# untitled.net
KiCad netlist of a schematic drawn in EAGLE
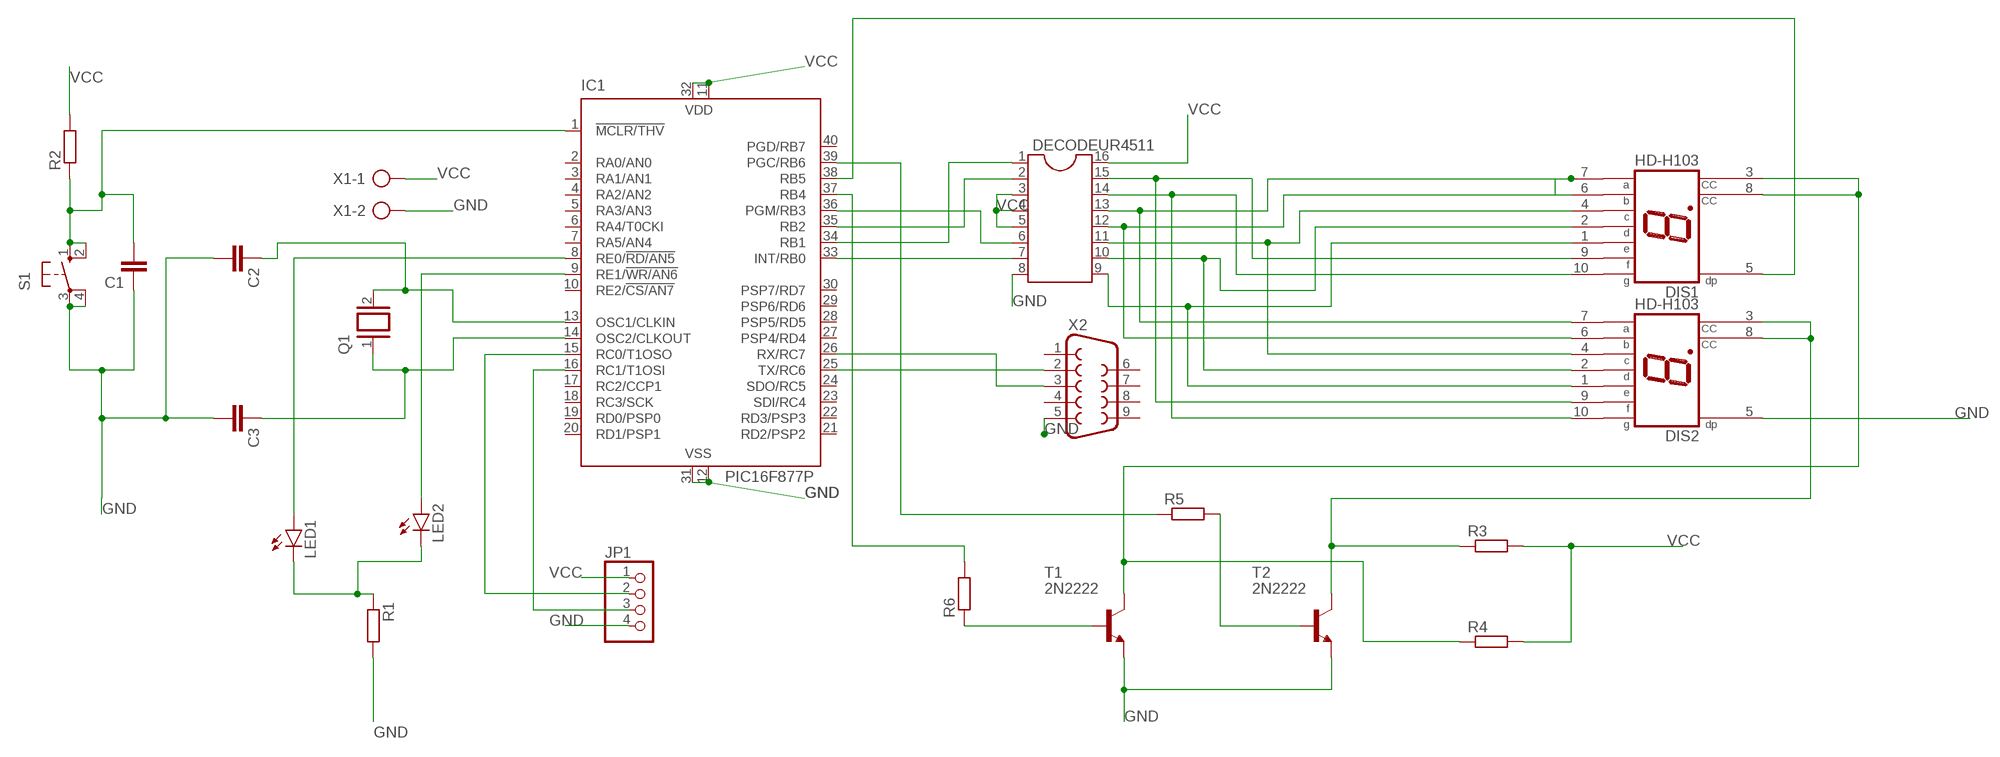
[diagram p0: schematic, sheet 1]

(export (version "E")
  (design (tool "Eeschema 10.0.6"))
  (components
    (comp (ref "C1")
      (value "C-EU025-025X050")
      (footprint "eagle-import:C025-025X050")
      (libsource (lib "eagle-import") (part "C-EU025-025X050"))
    )
    (comp (ref "C2")
      (value "C-EU025-025X050")
      (footprint "eagle-import:C025-025X050")
      (libsource (lib "eagle-import") (part "C-EU025-025X050"))
    )
    (comp (ref "C3")
      (value "C-EU025-025X050")
      (footprint "eagle-import:C025-025X050")
      (libsource (lib "eagle-import") (part "C-EU025-025X050"))
    )
    (comp (ref "DECODEUR4511")
      (value "DIL16")
      (footprint "eagle-import:DIL16")
      (libsource (lib "eagle-import") (part "DIL16"))
    )
    (comp (ref "DIS1")
      (value "HD-H103")
      (footprint "eagle-import:HDSP-M")
      (libsource (lib "eagle-import") (part "HD-H103"))
    )
    (comp (ref "DIS2")
      (value "HD-H103")
      (footprint "eagle-import:HDSP-M")
      (libsource (lib "eagle-import") (part "HD-H103"))
    )
    (comp (ref "IC1")
      (value "PIC16F877P")
      (footprint "eagle-import:DIL40")
      (fields (field (name "MF") "MICROCHIP") (field (name "MPN") "PIC16F877-04/P"))
      (libsource (lib "eagle-import") (part "PIC16F87P7"))
    )
    (comp (ref "JP1")
      (value "PINHD-1X4")
      (footprint "eagle-import:1X04")
      (libsource (lib "eagle-import") (part "PINHD-1X4"))
    )
    (comp (ref "LED1")
      (value "LED5MM")
      (footprint "eagle-import:LED5MM")
      (libsource (lib "eagle-import") (part "LED5MM"))
    )
    (comp (ref "LED2")
      (value "LED5MM")
      (footprint "eagle-import:LED5MM")
      (libsource (lib "eagle-import") (part "LED5MM"))
    )
    (comp (ref "Q1")
      (value "XTAL/S")
      (footprint "eagle-import:QS")
      (libsource (lib "eagle-import") (part "XTAL/S"))
    )
    (comp (ref "R1")
      (value "R-EU_0207/10")
      (footprint "eagle-import:0207_10")
      (libsource (lib "eagle-import") (part "R-EU_0207/10"))
    )
    (comp (ref "R2")
      (value "R-EU_0207/10")
      (footprint "eagle-import:0207_10")
      (libsource (lib "eagle-import") (part "R-EU_0207/10"))
    )
    (comp (ref "R3")
      (value "R-EU_0207/10")
      (footprint "eagle-import:0207_10")
      (libsource (lib "eagle-import") (part "R-EU_0207/10"))
    )
    (comp (ref "R4")
      (value "R-EU_0207/10")
      (footprint "eagle-import:0207_10")
      (libsource (lib "eagle-import") (part "R-EU_0207/10"))
    )
    (comp (ref "R5")
      (value "R-EU_0207/10")
      (footprint "eagle-import:0207_10")
      (libsource (lib "eagle-import") (part "R-EU_0207/10"))
    )
    (comp (ref "R6")
      (value "R-EU_0207/10")
      (footprint "eagle-import:0207_10")
      (libsource (lib "eagle-import") (part "R-EU_0207/10"))
    )
    (comp (ref "S1")
      (value "10-XX")
      (footprint "eagle-import:B3F-10XX")
      (fields (field (name "MPN") "B3F-1000"))
      (libsource (lib "eagle-import") (part "10-XX"))
    )
    (comp (ref "T1")
      (value "2N2222")
      (footprint "eagle-import:TO18")
      (libsource (lib "eagle-import") (part "2N2222"))
    )
    (comp (ref "T2")
      (value "2N2222")
      (footprint "eagle-import:TO18")
      (libsource (lib "eagle-import") (part "2N2222"))
    )
    (comp (ref "X1")
      (value "AK300/2")
      (footprint "eagle-import:AK300_2")
      (libsource (lib "eagle-import") (part "AK300/2"))
    )
    (comp (ref "X2")
      (value "F09H")
      (footprint "eagle-import:F09H")
      (libsource (lib "eagle-import") (part "F09H"))
    )
  )
  (nets
    (net (code "1") (name "/GND") (class "Default")
      (node (ref "C1") (pin "1") (pinfunction "1_1") (pintype "passive"))
      (node (ref "C2") (pin "2") (pinfunction "2_2") (pintype "passive"))
      (node (ref "C3") (pin "2") (pinfunction "2_2") (pintype "passive"))
      (node (ref "DECODEUR4511") (pin "8") (pinfunction "8_8") (pintype "passive"))
      (node (ref "DIS2") (pin "5") (pinfunction "DP_5") (pintype "passive"))
      (node (ref "IC1") (pin "12") (pinfunction "VSS_12") (pintype "power_in"))
      (node (ref "IC1") (pin "31") (pinfunction "VSS_31") (pintype "power_in"))
      (node (ref "JP1") (pin "4") (pinfunction "4_4") (pintype "passive"))
      (node (ref "R1") (pin "2") (pinfunction "2_2") (pintype "passive"))
      (node (ref "S1") (pin "3") (pinfunction "P_3") (pintype "passive"))
      (node (ref "S1") (pin "4") (pinfunction "P1_4") (pintype "passive"))
      (node (ref "T1") (pin "1") (pinfunction "E_1") (pintype "passive"))
      (node (ref "T2") (pin "1") (pinfunction "E_1") (pintype "passive"))
      (node (ref "X1") (pin "2") (pinfunction "KL_2") (pintype "passive"))
      (node (ref "X2") (pin "5") (pinfunction "5_5") (pintype "passive"))
    )
    (net (code "2") (name "/VCC") (class "Default")
      (node (ref "DECODEUR4511") (pin "16") (pinfunction "16_16") (pintype "passive"))
      (node (ref "DECODEUR4511") (pin "3") (pinfunction "3_3") (pintype "passive"))
      (node (ref "DECODEUR4511") (pin "4") (pinfunction "4_4") (pintype "passive"))
      (node (ref "DECODEUR4511") (pin "5") (pinfunction "5_5") (pintype "passive"))
      (node (ref "IC1") (pin "11") (pinfunction "VDD_11") (pintype "power_in"))
      (node (ref "IC1") (pin "32") (pinfunction "VDD_32") (pintype "power_in"))
      (node (ref "JP1") (pin "1") (pinfunction "1_1") (pintype "passive"))
      (node (ref "R2") (pin "2") (pinfunction "2_2") (pintype "passive"))
      (node (ref "R3") (pin "2") (pinfunction "2_2") (pintype "passive"))
      (node (ref "R4") (pin "2") (pinfunction "2_2") (pintype "passive"))
      (node (ref "X1") (pin "1") (pinfunction "KL_1") (pintype "passive"))
    )
    (net (code "3") (name "Net-(DIS1-A)") (class "Default")
      (node (ref "DECODEUR4511") (pin "13") (pinfunction "13_13") (pintype "passive"))
      (node (ref "DIS1") (pin "7") (pinfunction "A_7") (pintype "passive"))
      (node (ref "DIS2") (pin "7") (pinfunction "A_7") (pintype "passive"))
    )
    (net (code "4") (name "Net-(DIS1-B)") (class "Default")
      (node (ref "DECODEUR4511") (pin "12") (pinfunction "12_12") (pintype "passive"))
      (node (ref "DIS1") (pin "6") (pinfunction "B_6") (pintype "passive"))
      (node (ref "DIS2") (pin "6") (pinfunction "B_6") (pintype "passive"))
    )
    (net (code "5") (name "Net-(DIS1-C)") (class "Default")
      (node (ref "DECODEUR4511") (pin "11") (pinfunction "11_11") (pintype "passive"))
      (node (ref "DIS1") (pin "4") (pinfunction "C_4") (pintype "passive"))
      (node (ref "DIS2") (pin "4") (pinfunction "C_4") (pintype "passive"))
    )
    (net (code "6") (name "Net-(DIS1-D)") (class "Default")
      (node (ref "DECODEUR4511") (pin "10") (pinfunction "10_10") (pintype "passive"))
      (node (ref "DIS1") (pin "2") (pinfunction "D_2") (pintype "passive"))
      (node (ref "DIS2") (pin "2") (pinfunction "D_2") (pintype "passive"))
    )
    (net (code "7") (name "Net-(DIS1-DP)") (class "Default")
      (node (ref "DIS1") (pin "5") (pinfunction "DP_5") (pintype "passive"))
      (node (ref "IC1") (pin "38") (pinfunction "RB5_38") (pintype "bidirectional"))
    )
    (net (code "8") (name "Net-(DIS1-E)") (class "Default")
      (node (ref "DECODEUR4511") (pin "9") (pinfunction "9_9") (pintype "passive"))
      (node (ref "DIS1") (pin "1") (pinfunction "E_1") (pintype "passive"))
      (node (ref "DIS2") (pin "1") (pinfunction "E_1") (pintype "passive"))
    )
    (net (code "9") (name "Net-(DIS1-F)") (class "Default")
      (node (ref "DECODEUR4511") (pin "15") (pinfunction "15_15") (pintype "passive"))
      (node (ref "DIS1") (pin "9") (pinfunction "F_9") (pintype "passive"))
      (node (ref "DIS2") (pin "9") (pinfunction "F_9") (pintype "passive"))
    )
    (net (code "10") (name "Net-(DIS1-G)") (class "Default")
      (node (ref "DECODEUR4511") (pin "14") (pinfunction "14_14") (pintype "passive"))
      (node (ref "DIS1") (pin "10") (pinfunction "G_10") (pintype "passive"))
      (node (ref "DIS2") (pin "10") (pinfunction "G_10") (pintype "passive"))
    )
    (net (code "11") (name "Net-(IC1-INT{slash}RB0)") (class "Default")
      (node (ref "DECODEUR4511") (pin "7") (pinfunction "7_7") (pintype "passive"))
      (node (ref "IC1") (pin "33") (pinfunction "INT/RB0_33") (pintype "bidirectional"))
    )
    (net (code "12") (name "Net-(IC1-OSC1{slash}CLKIN)") (class "Default")
      (node (ref "C2") (pin "1") (pinfunction "1_1") (pintype "passive"))
      (node (ref "IC1") (pin "13") (pinfunction "OSC1/CLKIN_13") (pintype "input"))
      (node (ref "Q1") (pin "2") (pinfunction "2_2") (pintype "passive"))
    )
    (net (code "13") (name "Net-(IC1-OSC2{slash}CLKOUT)") (class "Default")
      (node (ref "C3") (pin "1") (pinfunction "1_1") (pintype "passive"))
      (node (ref "IC1") (pin "14") (pinfunction "OSC2/CLKOUT_14") (pintype "output"))
      (node (ref "Q1") (pin "1") (pinfunction "1_1") (pintype "passive"))
    )
    (net (code "14") (name "Net-(IC1-PGC{slash}RB6)") (class "Default")
      (node (ref "IC1") (pin "39") (pinfunction "PGC/RB6_39") (pintype "bidirectional"))
      (node (ref "R5") (pin "1") (pinfunction "1_1") (pintype "passive"))
    )
    (net (code "15") (name "Net-(IC1-PGM{slash}RB3)") (class "Default")
      (node (ref "DECODEUR4511") (pin "6") (pinfunction "6_6") (pintype "passive"))
      (node (ref "IC1") (pin "36") (pinfunction "PGM/RB3_36") (pintype "bidirectional"))
    )
    (net (code "16") (name "Net-(IC1-RB1)") (class "Default")
      (node (ref "DECODEUR4511") (pin "1") (pinfunction "1_1") (pintype "passive"))
      (node (ref "IC1") (pin "34") (pinfunction "RB1_34") (pintype "bidirectional"))
    )
    (net (code "17") (name "Net-(IC1-RB2)") (class "Default")
      (node (ref "DECODEUR4511") (pin "2") (pinfunction "2_2") (pintype "passive"))
      (node (ref "IC1") (pin "35") (pinfunction "RB2_35") (pintype "bidirectional"))
    )
    (net (code "18") (name "Net-(IC1-RB4)") (class "Default")
      (node (ref "IC1") (pin "37") (pinfunction "RB4_37") (pintype "bidirectional"))
      (node (ref "R6") (pin "2") (pinfunction "2_2") (pintype "passive"))
    )
    (net (code "19") (name "Net-(IC1-RC0{slash}T1OSO)") (class "Default")
      (node (ref "IC1") (pin "15") (pinfunction "RC0/T1OSO_15") (pintype "bidirectional"))
      (node (ref "JP1") (pin "2") (pinfunction "2_2") (pintype "passive"))
    )
    (net (code "20") (name "Net-(IC1-RC1{slash}T1OSI)") (class "Default")
      (node (ref "IC1") (pin "16") (pinfunction "RC1/T1OSI_16") (pintype "bidirectional"))
      (node (ref "JP1") (pin "3") (pinfunction "3_3") (pintype "passive"))
    )
    (net (code "21") (name "Net-(IC1-RE0{slash}~{RD{slash}AN5})") (class "Default")
      (node (ref "IC1") (pin "8") (pinfunction "RE0/~{RD/AN5}_8") (pintype "bidirectional"))
      (node (ref "LED1") (pin "A") (pinfunction "A_A") (pintype "passive"))
    )
    (net (code "22") (name "Net-(IC1-RE1{slash}~{WR{slash}AN6})") (class "Default")
      (node (ref "IC1") (pin "9") (pinfunction "RE1/~{WR/AN6}_9") (pintype "bidirectional"))
      (node (ref "LED2") (pin "A") (pinfunction "A_A") (pintype "passive"))
    )
    (net (code "23") (name "Net-(IC1-RX{slash}RC7)") (class "Default")
      (node (ref "IC1") (pin "26") (pinfunction "RX/RC7_26") (pintype "bidirectional"))
      (node (ref "X2") (pin "3") (pinfunction "3_3") (pintype "passive"))
    )
    (net (code "24") (name "Net-(IC1-TX{slash}RC6)") (class "Default")
      (node (ref "IC1") (pin "25") (pinfunction "TX/RC6_25") (pintype "bidirectional"))
      (node (ref "X2") (pin "2") (pinfunction "2_2") (pintype "passive"))
    )
    (net (code "25") (name "Net-(IC1-~{MCLR{slash}THV})") (class "Default")
      (node (ref "C1") (pin "2") (pinfunction "2_2") (pintype "passive"))
      (node (ref "IC1") (pin "1") (pinfunction "~{MCLR/THV}_1") (pintype "input"))
      (node (ref "R2") (pin "1") (pinfunction "1_1") (pintype "passive"))
      (node (ref "S1") (pin "1") (pinfunction "S_1") (pintype "passive"))
      (node (ref "S1") (pin "2") (pinfunction "S1_2") (pintype "passive"))
    )
    (net (code "26") (name "Net-(LED1-C)") (class "Default")
      (node (ref "LED1") (pin "K") (pinfunction "C_K") (pintype "passive"))
      (node (ref "LED2") (pin "K") (pinfunction "C_K") (pintype "passive"))
      (node (ref "R1") (pin "1") (pinfunction "1_1") (pintype "passive"))
    )
    (net (code "27") (name "Net-(T1-B)") (class "Default")
      (node (ref "R6") (pin "1") (pinfunction "1_1") (pintype "passive"))
      (node (ref "T1") (pin "2") (pinfunction "B_2") (pintype "passive"))
    )
    (net (code "28") (name "Net-(T1-C)") (class "Default")
      (node (ref "DIS1") (pin "3") (pinfunction "CC_3") (pintype "passive"))
      (node (ref "DIS1") (pin "8") (pinfunction "CC_8") (pintype "passive"))
      (node (ref "R4") (pin "1") (pinfunction "1_1") (pintype "passive"))
      (node (ref "T1") (pin "3") (pinfunction "C_3") (pintype "passive"))
    )
    (net (code "29") (name "Net-(T2-B)") (class "Default")
      (node (ref "R5") (pin "2") (pinfunction "2_2") (pintype "passive"))
      (node (ref "T2") (pin "2") (pinfunction "B_2") (pintype "passive"))
    )
    (net (code "30") (name "Net-(T2-C)") (class "Default")
      (node (ref "DIS2") (pin "3") (pinfunction "CC_3") (pintype "passive"))
      (node (ref "DIS2") (pin "8") (pinfunction "CC_8") (pintype "passive"))
      (node (ref "R3") (pin "1") (pinfunction "1_1") (pintype "passive"))
      (node (ref "T2") (pin "3") (pinfunction "C_3") (pintype "passive"))
    )
    (net (code "31") (name "unconnected-(IC1-PGD{slash}RB7-Pad40)") (class "Default")
      (node (ref "IC1") (pin "40") (pinfunction "PGD/RB7_40") (pintype "bidirectional"))
    )
    (net (code "32") (name "unconnected-(IC1-PSP4{slash}RD4-Pad27)") (class "Default")
      (node (ref "IC1") (pin "27") (pinfunction "PSP4/RD4_27") (pintype "bidirectional"))
    )
    (net (code "33") (name "unconnected-(IC1-PSP5{slash}RD5-Pad28)") (class "Default")
      (node (ref "IC1") (pin "28") (pinfunction "PSP5/RD5_28") (pintype "bidirectional"))
    )
    (net (code "34") (name "unconnected-(IC1-PSP6{slash}RD6-Pad29)") (class "Default")
      (node (ref "IC1") (pin "29") (pinfunction "PSP6/RD6_29") (pintype "bidirectional"))
    )
    (net (code "35") (name "unconnected-(IC1-PSP7{slash}RD7-Pad30)") (class "Default")
      (node (ref "IC1") (pin "30") (pinfunction "PSP7/RD7_30") (pintype "bidirectional"))
    )
    (net (code "36") (name "unconnected-(IC1-RA0{slash}AN0-Pad2)") (class "Default")
      (node (ref "IC1") (pin "2") (pinfunction "RA0/AN0_2") (pintype "bidirectional"))
    )
    (net (code "37") (name "unconnected-(IC1-RA1{slash}AN1-Pad3)") (class "Default")
      (node (ref "IC1") (pin "3") (pinfunction "RA1/AN1_3") (pintype "bidirectional"))
    )
    (net (code "38") (name "unconnected-(IC1-RA2{slash}AN2-Pad4)") (class "Default")
      (node (ref "IC1") (pin "4") (pinfunction "RA2/AN2_4") (pintype "bidirectional"))
    )
    (net (code "39") (name "unconnected-(IC1-RA3{slash}AN3-Pad5)") (class "Default")
      (node (ref "IC1") (pin "5") (pinfunction "RA3/AN3_5") (pintype "bidirectional"))
    )
    (net (code "40") (name "unconnected-(IC1-RA4{slash}T0CKI-Pad6)") (class "Default")
      (node (ref "IC1") (pin "6") (pinfunction "RA4/T0CKI_6") (pintype "bidirectional"))
    )
    (net (code "41") (name "unconnected-(IC1-RA5{slash}AN4-Pad7)") (class "Default")
      (node (ref "IC1") (pin "7") (pinfunction "RA5/AN4_7") (pintype "bidirectional"))
    )
    (net (code "42") (name "unconnected-(IC1-RC2{slash}CCP1-Pad17)") (class "Default")
      (node (ref "IC1") (pin "17") (pinfunction "RC2/CCP1_17") (pintype "bidirectional"))
    )
    (net (code "43") (name "unconnected-(IC1-RC3{slash}SCK-Pad18)") (class "Default")
      (node (ref "IC1") (pin "18") (pinfunction "RC3/SCK_18") (pintype "bidirectional"))
    )
    (net (code "44") (name "unconnected-(IC1-RD0{slash}PSP0-Pad19)") (class "Default")
      (node (ref "IC1") (pin "19") (pinfunction "RD0/PSP0_19") (pintype "bidirectional"))
    )
    (net (code "45") (name "unconnected-(IC1-RD1{slash}PSP1-Pad20)") (class "Default")
      (node (ref "IC1") (pin "20") (pinfunction "RD1/PSP1_20") (pintype "bidirectional"))
    )
    (net (code "46") (name "unconnected-(IC1-RD2{slash}PSP2-Pad21)") (class "Default")
      (node (ref "IC1") (pin "21") (pinfunction "RD2/PSP2_21") (pintype "bidirectional"))
    )
    (net (code "47") (name "unconnected-(IC1-RD3{slash}PSP3-Pad22)") (class "Default")
      (node (ref "IC1") (pin "22") (pinfunction "RD3/PSP3_22") (pintype "bidirectional"))
    )
    (net (code "48") (name "unconnected-(IC1-RE2{slash}~{CS{slash}AN7}-Pad10)") (class "Default")
      (node (ref "IC1") (pin "10") (pinfunction "RE2/~{CS/AN7}_10") (pintype "bidirectional"))
    )
    (net (code "49") (name "unconnected-(IC1-SDI{slash}RC4-Pad23)") (class "Default")
      (node (ref "IC1") (pin "23") (pinfunction "SDI/RC4_23") (pintype "bidirectional"))
    )
    (net (code "50") (name "unconnected-(IC1-SDO{slash}RC5-Pad24)") (class "Default")
      (node (ref "IC1") (pin "24") (pinfunction "SDO/RC5_24") (pintype "bidirectional"))
    )
    (net (code "51") (name "unconnected-(X2-Pad1)") (class "Default")
      (node (ref "X2") (pin "1") (pinfunction "1_1") (pintype "passive"))
    )
    (net (code "52") (name "unconnected-(X2-Pad4)") (class "Default")
      (node (ref "X2") (pin "4") (pinfunction "4_4") (pintype "passive"))
    )
    (net (code "53") (name "unconnected-(X2-Pad6)") (class "Default")
      (node (ref "X2") (pin "6") (pinfunction "6_6") (pintype "passive"))
    )
    (net (code "54") (name "unconnected-(X2-Pad7)") (class "Default")
      (node (ref "X2") (pin "7") (pinfunction "7_7") (pintype "passive"))
    )
    (net (code "55") (name "unconnected-(X2-Pad8)") (class "Default")
      (node (ref "X2") (pin "8") (pinfunction "8_8") (pintype "passive"))
    )
    (net (code "56") (name "unconnected-(X2-Pad9)") (class "Default")
      (node (ref "X2") (pin "9") (pinfunction "9_9") (pintype "passive"))
    )
  )
)
